# AMU_Version_3.net
KiCad netlist of a schematic drawn in Altium Designer
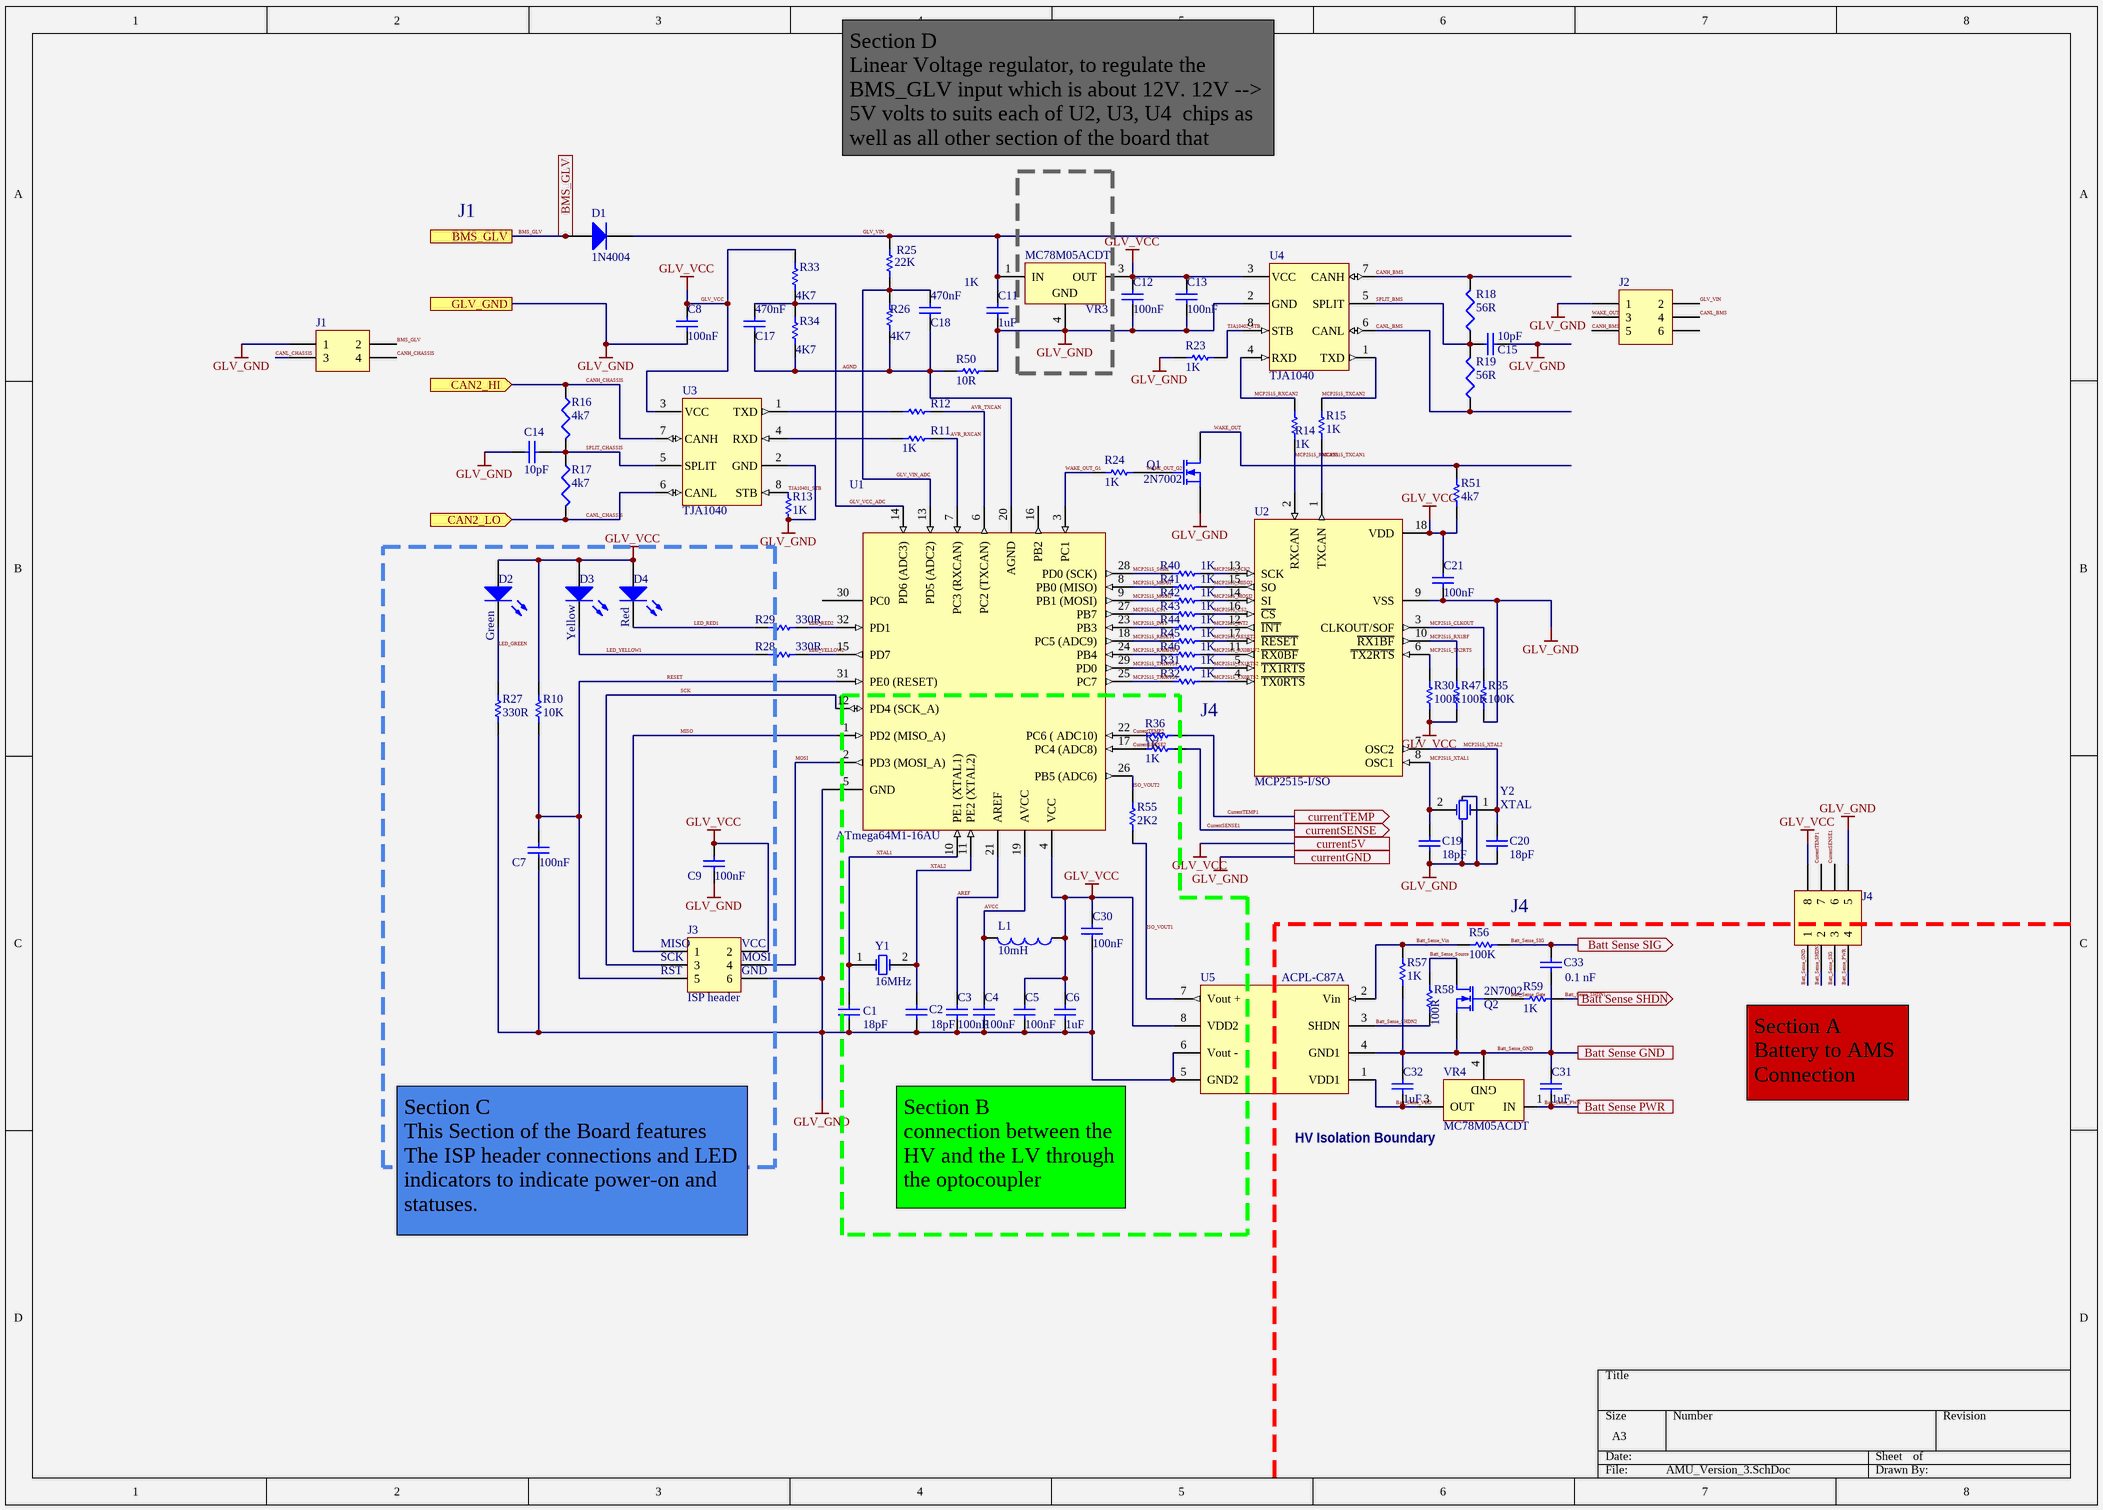
[diagram p0: AMU_Version_3.SchDoc]

(export (version "E")
  (design (tool "Eeschema 10.0.6"))
  (components
    (comp (ref "C1")
      (value "18pF")
      (footprint "1608[0603]")
      (description "Capacitor (Semiconductor SIM Model)")
      (fields (field (name "Comment") "Cap Semi") (field (name "PUBLISHER") "Altium Limited"))
      (libsource (lib "Miscellaneous Devices") (part "Cap Semi"))
    )
    (comp (ref "C2")
      (value "18pF")
      (footprint "1608[0603]")
      (description "Capacitor (Semiconductor SIM Model)")
      (fields (field (name "Comment") "Cap Semi") (field (name "PUBLISHER") "Altium Limited"))
      (libsource (lib "Miscellaneous Devices") (part "Cap Semi"))
    )
    (comp (ref "C3")
      (value "100nF")
      (footprint "1608[0603]")
      (description "Capacitor (Semiconductor SIM Model)")
      (fields (field (name "Comment") "Cap Semi") (field (name "PUBLISHER") "Altium Limited"))
      (libsource (lib "Miscellaneous Devices") (part "Cap Semi"))
    )
    (comp (ref "C4")
      (value "100nF")
      (footprint "1608[0603]")
      (description "Capacitor (Semiconductor SIM Model)")
      (fields (field (name "Comment") "Cap Semi") (field (name "PUBLISHER") "Altium Limited"))
      (libsource (lib "Miscellaneous Devices") (part "Cap Semi"))
    )
    (comp (ref "C5")
      (value "100nF")
      (footprint "1608[0603]")
      (description "Capacitor (Semiconductor SIM Model)")
      (fields (field (name "Comment") "Cap Semi") (field (name "PUBLISHER") "Altium Limited"))
      (libsource (lib "Miscellaneous Devices") (part "Cap Semi"))
    )
    (comp (ref "C6")
      (value "1uF")
      (footprint "1608[0603]")
      (description "Capacitor (Semiconductor SIM Model)")
      (fields (field (name "Comment") "Cap Semi") (field (name "PUBLISHER") "Altium Limited"))
      (libsource (lib "Miscellaneous Devices") (part "Cap Semi"))
    )
    (comp (ref "C7")
      (value "100nF")
      (footprint "1608[0603]")
      (description "Capacitor (Semiconductor SIM Model)")
      (fields (field (name "Comment") "Cap Semi") (field (name "PUBLISHER") "Altium Limited"))
      (libsource (lib "Miscellaneous Devices") (part "Cap Semi"))
    )
    (comp (ref "C8")
      (value "100nF")
      (footprint "1608[0603]")
      (description "Capacitor (Semiconductor SIM Model)")
      (fields (field (name "Comment") "Cap Semi") (field (name "PUBLISHER") "Altium Limited"))
      (libsource (lib "Miscellaneous Devices") (part "Cap Semi"))
    )
    (comp (ref "C9")
      (value "100nF")
      (footprint "1608[0603]")
      (description "Capacitor (Semiconductor SIM Model)")
      (fields (field (name "Comment") "Cap Semi") (field (name "PUBLISHER") "Altium Limited"))
      (libsource (lib "Miscellaneous Devices") (part "Cap Semi"))
    )
    (comp (ref "C11")
      (value "1uF")
      (footprint "1608[0603]")
      (description "Capacitor (Semiconductor SIM Model)")
      (fields (field (name "Comment") "Cap Semi") (field (name "PUBLISHER") "Altium Limited"))
      (libsource (lib "Miscellaneous Devices") (part "Cap Semi"))
    )
    (comp (ref "C12")
      (value "100nF")
      (footprint "1608[0603]")
      (description "Capacitor (Semiconductor SIM Model)")
      (fields (field (name "Comment") "Cap Semi") (field (name "PUBLISHER") "Altium Limited"))
      (libsource (lib "Miscellaneous Devices") (part "Cap Semi"))
    )
    (comp (ref "C13")
      (value "100nF")
      (footprint "1608[0603]")
      (description "Capacitor (Semiconductor SIM Model)")
      (fields (field (name "Comment") "Cap Semi") (field (name "PUBLISHER") "Altium Limited"))
      (libsource (lib "Miscellaneous Devices") (part "Cap Semi"))
    )
    (comp (ref "C14")
      (value "10pF")
      (footprint "1608[0603]")
      (description "Capacitor (Semiconductor SIM Model)")
      (fields (field (name "Comment") "Cap Semi") (field (name "PUBLISHER") "Altium Limited"))
      (libsource (lib "Miscellaneous Devices") (part "Cap Semi"))
    )
    (comp (ref "C15")
      (value "10pF")
      (footprint "1608[0603]")
      (description "Capacitor (Semiconductor SIM Model)")
      (fields (field (name "Comment") "Cap Semi") (field (name "PUBLISHER") "Altium Limited"))
      (libsource (lib "Miscellaneous Devices") (part "Cap Semi"))
    )
    (comp (ref "C17")
      (value "470nF")
      (footprint "1608[0603]")
      (description "Capacitor (Semiconductor SIM Model)")
      (fields (field (name "Comment") "Cap Semi") (field (name "PUBLISHER") "Altium Limited"))
      (libsource (lib "Miscellaneous Devices") (part "Cap Semi"))
    )
    (comp (ref "C18")
      (value "470nF")
      (footprint "1608[0603]")
      (description "Capacitor (Semiconductor SIM Model)")
      (fields (field (name "Comment") "Cap Semi") (field (name "PUBLISHER") "Altium Limited"))
      (libsource (lib "Miscellaneous Devices") (part "Cap Semi"))
    )
    (comp (ref "C19")
      (value "18pF")
      (footprint "1608[0603]")
      (description "Capacitor (Semiconductor SIM Model)")
      (fields (field (name "Comment") "Cap Semi") (field (name "PUBLISHER") "Altium Limited"))
      (libsource (lib "Miscellaneous Devices") (part "Cap Semi"))
    )
    (comp (ref "C20")
      (value "18pF")
      (footprint "1608[0603]")
      (description "Capacitor (Semiconductor SIM Model)")
      (fields (field (name "Comment") "Cap Semi") (field (name "PUBLISHER") "Altium Limited"))
      (libsource (lib "Miscellaneous Devices") (part "Cap Semi"))
    )
    (comp (ref "C21")
      (value "100nF")
      (footprint "1608[0603]")
      (description "Capacitor (Semiconductor SIM Model)")
      (fields (field (name "Comment") "Cap Semi") (field (name "PUBLISHER") "Altium Limited"))
      (libsource (lib "Miscellaneous Devices") (part "Cap Semi"))
    )
    (comp (ref "C30")
      (value "100nF")
      (footprint "1608[0603]")
      (description "Capacitor (Semiconductor SIM Model)")
      (fields (field (name "Comment") "Cap Semi") (field (name "PUBLISHER") "Altium Limited"))
      (libsource (lib "Miscellaneous Devices") (part "Cap Semi"))
    )
    (comp (ref "C31")
      (value "1uF")
      (footprint "1608[0603]")
      (description "Capacitor (Semiconductor SIM Model)")
      (fields (field (name "Comment") "Cap Semi") (field (name "PUBLISHER") "Altium Limited"))
      (libsource (lib "Miscellaneous Devices") (part "Cap Semi"))
    )
    (comp (ref "C32")
      (value "1uF")
      (footprint "1608[0603]")
      (description "Capacitor (Semiconductor SIM Model)")
      (fields (field (name "Comment") "Cap Semi") (field (name "PUBLISHER") "Altium Limited"))
      (libsource (lib "Miscellaneous Devices") (part "Cap Semi"))
    )
    (comp (ref "C33")
      (value "0.1 nF")
      (footprint "1608[0603]")
      (description "Capacitor (Semiconductor SIM Model)")
      (fields (field (name "Comment") "Cap Semi") (field (name "PUBLISHER") "Altium Limited"))
      (libsource (lib "Miscellaneous Devices") (part "Cap Semi"))
    )
    (comp (ref "D1")
      (value "1N4004")
      (footprint "PCBComponent_1")
      (description "Default Diode")
      (fields (field (name "PUBLISHER") "Altium Limited"))
      (libsource (lib "Miscellaneous Devices") (part "Diode"))
    )
    (comp (ref "D2")
      (value "Green")
      (footprint "0805_A")
      (description "Typical RED, GREEN, YELLOW, AMBER GaAs LED")
      (fields (field (name "PUBLISHER") "Altium Limited"))
      (libsource (lib "Miscellaneous Devices") (part "LED2"))
    )
    (comp (ref "D3")
      (value "Yellow")
      (footprint "0805_A")
      (description "Typical RED, GREEN, YELLOW, AMBER GaAs LED")
      (fields (field (name "PUBLISHER") "Altium Limited"))
      (libsource (lib "Miscellaneous Devices") (part "LED2"))
    )
    (comp (ref "D4")
      (value "Red")
      (footprint "0805_A")
      (description "Typical RED, GREEN, YELLOW, AMBER GaAs LED")
      (fields (field (name "PUBLISHER") "Altium Limited"))
      (libsource (lib "Miscellaneous Devices") (part "LED2"))
    )
    (comp (ref "J1")
      (value "Header 2X2")
      (footprint "HDR2X2")
      (description "Header, 2-Pin, Dual row")
      (fields (field (name "PUBLISHER") "Altium Limited"))
      (libsource (lib "Miscellaneous Connectors") (part "Header 2X2"))
    )
    (comp (ref "J2")
      (value "Header 3X2")
      (footprint "HDR2X3")
      (description "Header, 3-Pin, Dual row")
      (fields (field (name "PUBLISHER") "Altium Limited"))
      (libsource (lib "Miscellaneous Connectors") (part "Header 3X2"))
    )
    (comp (ref "J3")
      (value "ISP header")
      (footprint "HDR2X3")
      (description "Header, 3-Pin, Dual row")
      (fields (field (name "PUBLISHER") "Altium Limited"))
      (libsource (lib "Miscellaneous Connectors") (part "Header 3X2"))
    )
    (comp (ref "J4")
      (value "Header 4X2")
      (footprint "Miscellaneous Connectors:HDR2X4_CEN")
      (description "Header, 4-Pin, Dual row")
      (fields (field (name "PUBLISHER") "Altium Limited"))
      (libsource (lib "altium-import") (part "root_1_Header 4X2_"))
    )
    (comp (ref "L1")
      (value "10mH")
      (footprint "1608[0603]")
      (description "Inductor")
      (fields (field (name "PUBLISHER") "Altium Limited"))
      (libsource (lib "Miscellaneous Devices") (part "Inductor"))
    )
    (comp (ref "Q1")
      (value "2N7002")
      (footprint "SOT-23_N")
      (description "N-Channel MOSFET")
      (fields
        (field (name "MANUFACTURER") "NXP Semiconductors")
        (field (name "MANUFACTURER PART NUMBER") "2N7002P,215")
        (field (name "PUBLISHER") "Altium Limited")
      )
      (libsource (lib "") (part "MOSFET-N_1"))
    )
    (comp (ref "Q2")
      (value "2N7002")
      (footprint "SOT-23_L")
      (description "N-Channel MOSFET")
      (fields (field (name "PUBLISHER") "Altium Limited"))
      (libsource (lib "Miscellaneous Devices") (part "MOSFET-N"))
    )
    (comp (ref "R10")
      (value "10K")
      (footprint "6-0805_L")
      (description "Resistor")
      (fields (field (name "Comment") "Res1") (field (name "PUBLISHER") "Altium Limited"))
      (libsource (lib "Miscellaneous Devices") (part "Res1"))
    )
    (comp (ref "R11")
      (value "1K")
      (footprint "6-0805_L")
      (description "Resistor")
      (fields (field (name "Comment") "Res1") (field (name "PUBLISHER") "Altium Limited"))
      (libsource (lib "Miscellaneous Devices") (part "Res1"))
    )
    (comp (ref "R12")
      (value "1K")
      (footprint "6-0805_L")
      (description "Resistor")
      (fields (field (name "Comment") "Res1") (field (name "PUBLISHER") "Altium Limited"))
      (libsource (lib "Miscellaneous Devices") (part "Res1"))
    )
    (comp (ref "R13")
      (value "1K")
      (footprint "6-0805_L")
      (description "Resistor")
      (fields (field (name "Comment") "Res1") (field (name "PUBLISHER") "Altium Limited"))
      (libsource (lib "") (part "Res1_1"))
    )
    (comp (ref "R14")
      (value "1K")
      (footprint "6-0805_L")
      (description "Resistor")
      (fields (field (name "Comment") "Res1") (field (name "PUBLISHER") "Altium Limited"))
      (libsource (lib "Miscellaneous Devices") (part "Res1"))
    )
    (comp (ref "R15")
      (value "1K")
      (footprint "6-0805_L")
      (description "Resistor")
      (fields (field (name "Comment") "Res1") (field (name "PUBLISHER") "Altium Limited"))
      (libsource (lib "Miscellaneous Devices") (part "Res1"))
    )
    (comp (ref "R16")
      (value "4k7")
      (footprint "6-0805_L")
      (description "Resistor")
      (fields (field (name "Comment") "Res3") (field (name "PUBLISHER") "Altium Limited"))
      (libsource (lib "Miscellaneous Devices") (part "Res3"))
    )
    (comp (ref "R17")
      (value "4k7")
      (footprint "6-0805_L")
      (description "Resistor")
      (fields (field (name "Comment") "Res3") (field (name "PUBLISHER") "Altium Limited"))
      (libsource (lib "Miscellaneous Devices") (part "Res3"))
    )
    (comp (ref "R18")
      (value "56R")
      (footprint "6-0805_L")
      (description "Resistor")
      (fields (field (name "Comment") "Res3") (field (name "PUBLISHER") "Altium Limited"))
      (libsource (lib "Miscellaneous Devices") (part "Res3"))
    )
    (comp (ref "R19")
      (value "56R")
      (footprint "6-0805_L")
      (description "Resistor")
      (fields (field (name "Comment") "Res3") (field (name "PUBLISHER") "Altium Limited"))
      (libsource (lib "Miscellaneous Devices") (part "Res3"))
    )
    (comp (ref "R23")
      (value "1K")
      (footprint "6-0805_L")
      (description "Resistor")
      (fields (field (name "Comment") "Res1") (field (name "PUBLISHER") "Altium Limited"))
      (libsource (lib "Miscellaneous Devices") (part "Res1"))
    )
    (comp (ref "R24")
      (value "1K")
      (footprint "6-0805_L")
      (description "Resistor")
      (fields (field (name "Comment") "Res1") (field (name "PUBLISHER") "Altium Limited"))
      (libsource (lib "Miscellaneous Devices") (part "Res1"))
    )
    (comp (ref "R25")
      (value "22K")
      (footprint "6-0805_L")
      (description "Resistor")
      (fields (field (name "Comment") "Res1") (field (name "PUBLISHER") "Altium Limited"))
      (libsource (lib "Miscellaneous Devices") (part "Res1"))
    )
    (comp (ref "R26")
      (value "4K7")
      (footprint "6-0805_L")
      (description "Resistor")
      (fields (field (name "Comment") "Res1") (field (name "PUBLISHER") "Altium Limited"))
      (libsource (lib "Miscellaneous Devices") (part "Res1"))
    )
    (comp (ref "R27")
      (value "330R")
      (footprint "6-0805_L")
      (description "Resistor")
      (fields (field (name "Comment") "Res1") (field (name "PUBLISHER") "Altium Limited"))
      (libsource (lib "Miscellaneous Devices") (part "Res1"))
    )
    (comp (ref "R28")
      (value "330R")
      (footprint "6-0805_L")
      (description "Resistor")
      (fields (field (name "Comment") "Res1") (field (name "PUBLISHER") "Altium Limited"))
      (libsource (lib "Miscellaneous Devices") (part "Res1"))
    )
    (comp (ref "R29")
      (value "330R")
      (footprint "6-0805_L")
      (description "Resistor")
      (fields (field (name "Comment") "Res1") (field (name "PUBLISHER") "Altium Limited"))
      (libsource (lib "Miscellaneous Devices") (part "Res1"))
    )
    (comp (ref "R30")
      (value "100K")
      (footprint "6-0805_L")
      (description "Resistor")
      (fields (field (name "Comment") "Res1") (field (name "PUBLISHER") "Altium Limited"))
      (libsource (lib "Miscellaneous Devices") (part "Res1"))
    )
    (comp (ref "R31")
      (value "1K")
      (footprint "6-0805_L")
      (description "Resistor")
      (fields (field (name "Comment") "Res1") (field (name "PUBLISHER") "Altium Limited"))
      (libsource (lib "Miscellaneous Devices") (part "Res1"))
    )
    (comp (ref "R32")
      (value "1K")
      (footprint "6-0805_L")
      (description "Resistor")
      (fields (field (name "Comment") "Res1") (field (name "PUBLISHER") "Altium Limited"))
      (libsource (lib "Miscellaneous Devices") (part "Res1"))
    )
    (comp (ref "R33")
      (value "4K7")
      (footprint "6-0805_L")
      (description "Resistor")
      (fields (field (name "Comment") "Res1") (field (name "PUBLISHER") "Altium Limited"))
      (libsource (lib "Miscellaneous Devices") (part "Res1"))
    )
    (comp (ref "R34")
      (value "4K7")
      (footprint "6-0805_L")
      (description "Resistor")
      (fields (field (name "Comment") "Res1") (field (name "PUBLISHER") "Altium Limited"))
      (libsource (lib "Miscellaneous Devices") (part "Res1"))
    )
    (comp (ref "R35")
      (value "100K")
      (footprint "6-0805_L")
      (description "Resistor")
      (fields (field (name "Comment") "Res1") (field (name "PUBLISHER") "Altium Limited"))
      (libsource (lib "Miscellaneous Devices") (part "Res1"))
    )
    (comp (ref "R36")
      (value "1K")
      (footprint "6-0805_L")
      (description "Resistor")
      (fields (field (name "Comment") "Res1") (field (name "PUBLISHER") "Altium Limited"))
      (libsource (lib "Miscellaneous Devices") (part "Res1"))
    )
    (comp (ref "R37")
      (value "1K")
      (footprint "6-0805_L")
      (description "Resistor")
      (fields (field (name "Comment") "Res1") (field (name "PUBLISHER") "Altium Limited"))
      (libsource (lib "Miscellaneous Devices") (part "Res1"))
    )
    (comp (ref "R40")
      (value "1K")
      (footprint "6-0805_L")
      (description "Resistor")
      (fields (field (name "Comment") "Res1") (field (name "PUBLISHER") "Altium Limited"))
      (libsource (lib "Miscellaneous Devices") (part "Res1"))
    )
    (comp (ref "R41")
      (value "1K")
      (footprint "6-0805_L")
      (description "Resistor")
      (fields (field (name "Comment") "Res1") (field (name "PUBLISHER") "Altium Limited"))
      (libsource (lib "Miscellaneous Devices") (part "Res1"))
    )
    (comp (ref "R42")
      (value "1K")
      (footprint "6-0805_L")
      (description "Resistor")
      (fields (field (name "Comment") "Res1") (field (name "PUBLISHER") "Altium Limited"))
      (libsource (lib "Miscellaneous Devices") (part "Res1"))
    )
    (comp (ref "R43")
      (value "1K")
      (footprint "6-0805_L")
      (description "Resistor")
      (fields (field (name "Comment") "Res1") (field (name "PUBLISHER") "Altium Limited"))
      (libsource (lib "Miscellaneous Devices") (part "Res1"))
    )
    (comp (ref "R44")
      (value "1K")
      (footprint "6-0805_L")
      (description "Resistor")
      (fields (field (name "Comment") "Res1") (field (name "PUBLISHER") "Altium Limited"))
      (libsource (lib "Miscellaneous Devices") (part "Res1"))
    )
    (comp (ref "R45")
      (value "1K")
      (footprint "6-0805_L")
      (description "Resistor")
      (fields (field (name "Comment") "Res1") (field (name "PUBLISHER") "Altium Limited"))
      (libsource (lib "Miscellaneous Devices") (part "Res1"))
    )
    (comp (ref "R46")
      (value "1K")
      (footprint "6-0805_L")
      (description "Resistor")
      (fields (field (name "Comment") "Res1") (field (name "PUBLISHER") "Altium Limited"))
      (libsource (lib "Miscellaneous Devices") (part "Res1"))
    )
    (comp (ref "R47")
      (value "100K")
      (footprint "6-0805_L")
      (description "Resistor")
      (fields (field (name "Comment") "Res1") (field (name "PUBLISHER") "Altium Limited"))
      (libsource (lib "Miscellaneous Devices") (part "Res1"))
    )
    (comp (ref "R50")
      (value "10R")
      (footprint "6-0805_L")
      (description "Resistor")
      (fields (field (name "Comment") "Res1") (field (name "PUBLISHER") "Altium Limited"))
      (libsource (lib "Miscellaneous Devices") (part "Res1"))
    )
    (comp (ref "R51")
      (value "4k7")
      (footprint "6-0805_L")
      (description "Resistor")
      (fields (field (name "Comment") "Res1") (field (name "PUBLISHER") "Altium Limited"))
      (libsource (lib "Miscellaneous Devices") (part "Res1"))
    )
    (comp (ref "R55")
      (value "2K2")
      (footprint "6-0805_L")
      (description "Resistor")
      (fields (field (name "Comment") "Res1") (field (name "PUBLISHER") "Altium Limited"))
      (libsource (lib "Miscellaneous Devices") (part "Res1"))
    )
    (comp (ref "R56")
      (value "100K")
      (footprint "6-0805_L")
      (description "Resistor")
      (fields (field (name "Comment") "Res1") (field (name "PUBLISHER") "Altium Limited"))
      (libsource (lib "Miscellaneous Devices") (part "Res1"))
    )
    (comp (ref "R57")
      (value "1K")
      (footprint "6-0805_L")
      (description "Resistor")
      (fields (field (name "Comment") "Res1") (field (name "PUBLISHER") "Altium Limited"))
      (libsource (lib "Miscellaneous Devices") (part "Res1"))
    )
    (comp (ref "R58")
      (value "100R")
      (footprint "6-0805_L")
      (description "Resistor")
      (fields (field (name "Comment") "Res1") (field (name "PUBLISHER") "Altium Limited"))
      (libsource (lib "Miscellaneous Devices") (part "Res1"))
    )
    (comp (ref "R59")
      (value "1K")
      (footprint "6-0805_L")
      (description "Resistor")
      (fields (field (name "Comment") "Res1") (field (name "PUBLISHER") "Altium Limited"))
      (libsource (lib "Miscellaneous Devices") (part "Res1"))
    )
    (comp (ref "U1")
      (value "ATmega64M1-16AU")
      (footprint "32A_L")
      (description "8-Bit AVR Microcontroller with 8K Bytes of In-System Programmable Flash Memory")
      (fields (field (name "PUBLISHER") "Altium Limited"))
      (libsource (lib "Atmel Microcontroller 8-Bit AVR") (part "ATmega8-16AC"))
    )
    (comp (ref "U2")
      (value "MCP2515-I/SO")
      (footprint "MCP2515-I_SO:SOIC-SO18_M")
      (description "Stand-Alone CAN Controller With SPI Interface, 18-Pin SOIC, Industrial Temperature")
      (fields (field (name "PUBLISHER") "Altium Limited"))
      (libsource (lib "Microchip Interface") (part "MCP2515-I/SO"))
    )
    (comp (ref "U3")
      (value "TJA1040")
      (footprint "IC_NXP_TJA1040T-CM,118_eec_0:NXP_SOT96-1_0")
      (libsource (lib "IC_NXP_TJA1040T-CM,118_eec") (part "TJA1040"))
    )
    (comp (ref "U4")
      (value "TJA1040")
      (footprint "NXP_SOT96-1_0")
      (libsource (lib "Schlib1") (part "TJA1040"))
    )
    (comp (ref "U5")
      (value "ACPL-C87A")
      (footprint "Broadcom_SSO-8_IPC_A")
      (description "Isolated CAN transceiver")
      (fields (field (name "PUBLISHER") "Altium Limited"))
      (libsource (lib "Atmel Microcontroller 8-Bit AVR") (part "AT90S2343-10SI"))
    )
    (comp (ref "VR3")
      (value "MC78M05ACDT")
      (footprint "MC78M05ACDT")
      (description "Three-Terminal Medium Current Positive Voltage Regulator")
      (fields (field (name "PUBLISHER") "Altium Limited"))
      (libsource (lib "") (part "MC78M05ACDT_1"))
    )
    (comp (ref "VR4")
      (value "MC78M05ACDT")
      (footprint "MC78M05ACDT")
      (description "Three-Terminal Medium Current Positive Voltage Regulator")
      (fields (field (name "PUBLISHER") "Altium Limited"))
      (libsource (lib "ON Semi Power Mgt Voltage Regulator") (part "MC78M05ACDT"))
    )
    (comp (ref "Y1")
      (value "16MHz")
      (footprint "Crystal_Oscillator")
      (description "Crystal Oscillator")
      (fields (field (name "PUBLISHER") "Altium Limited"))
      (libsource (lib "Miscellaneous Devices") (part "XTAL"))
    )
    (comp (ref "Y2")
      (value "XTAL")
      (footprint "*XTAL_ECS-160-12-33Q-JES-TR")
      (description "Crystal Oscillator")
      (fields (field (name "PUBLISHER") "Altium Limited"))
      (libsource (lib "Schlib1") (part "XTAL"))
    )
  )
  (nets
    (net (code "1") (name "/AGND") (class "Default")
      (node (ref "C17") (pin "1") (pinfunction "1_1") (pintype "passive"))
      (node (ref "C18") (pin "1") (pinfunction "1_1") (pintype "passive"))
      (node (ref "R26") (pin "2") (pinfunction "2_2") (pintype "passive"))
      (node (ref "R34") (pin "2") (pinfunction "2_2") (pintype "passive"))
      (node (ref "R50") (pin "1") (pinfunction "1_1") (pintype "passive"))
      (node (ref "U1") (pin "20") (pinfunction "AGND_20") (pintype "power_in"))
    )
    (net (code "2") (name "/AREF") (class "Default")
      (node (ref "C3") (pin "1") (pinfunction "1_1") (pintype "passive"))
      (node (ref "U1") (pin "21") (pinfunction "AREF_21") (pintype "power_in"))
    )
    (net (code "3") (name "/AVCC") (class "Default")
      (node (ref "C4") (pin "1") (pinfunction "1_1") (pintype "passive"))
      (node (ref "L1") (pin "2") (pinfunction "2_2") (pintype "passive"))
      (node (ref "U1") (pin "19") (pinfunction "AVCC_19") (pintype "power_in"))
    )
    (net (code "4") (name "/AVR_RXCAN") (class "Default")
      (node (ref "R11") (pin "2") (pinfunction "2_2") (pintype "passive"))
      (node (ref "U1") (pin "7") (pinfunction "PC3_(RXCAN)_7") (pintype "input"))
    )
    (net (code "5") (name "/AVR_TXCAN") (class "Default")
      (node (ref "R12") (pin "1") (pinfunction "1_1") (pintype "passive"))
      (node (ref "U1") (pin "6") (pinfunction "PC2_(TXCAN)_6") (pintype "output"))
    )
    (net (code "6") (name "/BMS_GLV") (class "Default")
      (node (ref "D1") (pin "1") (pinfunction "A_1") (pintype "passive"))
      (node (ref "J1") (pin "2") (pinfunction "2_2") (pintype "passive"))
    )
    (net (code "7") (name "/Batt_Sense_GND") (class "Default")
      (node (ref "C31") (pin "2") (pinfunction "2_2") (pintype "passive"))
      (node (ref "C32") (pin "2") (pinfunction "2_2") (pintype "passive"))
      (node (ref "C33") (pin "1") (pinfunction "1_1") (pintype "passive"))
      (node (ref "J4") (pin "1") (pinfunction "1_1") (pintype "passive"))
      (node (ref "Q2") (pin "2") (pinfunction "S_2") (pintype "passive"))
      (node (ref "R57") (pin "1") (pinfunction "1_1") (pintype "passive"))
      (node (ref "U5") (pin "4") (pinfunction "GND1_4") (pintype "power_in"))
      (node (ref "VR4") (pin "4") (pinfunction "GND_4") (pintype "power_in"))
    )
    (net (code "8") (name "/Batt_Sense_Gate") (class "Default")
      (node (ref "Q2") (pin "1") (pinfunction "G_1") (pintype "passive"))
      (node (ref "R59") (pin "2") (pinfunction "2_2") (pintype "passive"))
    )
    (net (code "9") (name "/Batt_Sense_PWR") (class "Default")
      (node (ref "C31") (pin "1") (pinfunction "1_1") (pintype "passive"))
      (node (ref "J4") (pin "4") (pinfunction "4_4") (pintype "passive"))
      (node (ref "VR4") (pin "1") (pinfunction "IN_1") (pintype "power_in"))
    )
    (net (code "10") (name "/Batt_Sense_SHDN1") (class "Default")
      (node (ref "J4") (pin "2") (pinfunction "2_2") (pintype "passive"))
      (node (ref "R59") (pin "1") (pinfunction "1_1") (pintype "passive"))
    )
    (net (code "11") (name "/Batt_Sense_SHDN2") (class "Default")
      (node (ref "R58") (pin "1") (pinfunction "1_1") (pintype "passive"))
      (node (ref "U5") (pin "3") (pinfunction "SHDN_3") (pintype "open_collector"))
    )
    (net (code "12") (name "/Batt_Sense_SIG") (class "Default")
      (node (ref "C33") (pin "2") (pinfunction "2_2") (pintype "passive"))
      (node (ref "J4") (pin "3") (pinfunction "3_3") (pintype "passive"))
      (node (ref "R56") (pin "1") (pinfunction "1_1") (pintype "passive"))
    )
    (net (code "13") (name "/Batt_Sense_Source") (class "Default")
      (node (ref "Q2") (pin "3") (pinfunction "D_3") (pintype "passive"))
      (node (ref "R58") (pin "2") (pinfunction "2_2") (pintype "passive"))
    )
    (net (code "14") (name "/Batt_Sense_VDD") (class "Default")
      (node (ref "C32") (pin "1") (pinfunction "1_1") (pintype "passive"))
      (node (ref "U5") (pin "1") (pinfunction "VDD1_1") (pintype "power_in"))
      (node (ref "VR4") (pin "3") (pinfunction "OUT_3") (pintype "power_in"))
    )
    (net (code "15") (name "/Batt_Sense_Vin") (class "Default")
      (node (ref "R56") (pin "2") (pinfunction "2_2") (pintype "passive"))
      (node (ref "R57") (pin "2") (pinfunction "2_2") (pintype "passive"))
      (node (ref "U5") (pin "2") (pinfunction "Vin_2") (pintype "input"))
    )
    (net (code "16") (name "/CANH_BMS") (class "Default")
      (node (ref "J2") (pin "5") (pinfunction "5_5") (pintype "passive"))
      (node (ref "R18") (pin "2") (pinfunction "2_2") (pintype "passive"))
      (node (ref "U4") (pin "7") (pinfunction "CANH_7") (pintype "bidirectional"))
    )
    (net (code "17") (name "/CANH_CHASSIS") (class "Default")
      (node (ref "J1") (pin "4") (pinfunction "4_4") (pintype "passive"))
      (node (ref "R16") (pin "1") (pinfunction "1_1") (pintype "passive"))
      (node (ref "U3") (pin "7") (pinfunction "CANH_7") (pintype "bidirectional"))
    )
    (net (code "18") (name "/CANL_BMS") (class "Default")
      (node (ref "J2") (pin "4") (pinfunction "4_4") (pintype "passive"))
      (node (ref "R19") (pin "1") (pinfunction "1_1") (pintype "passive"))
      (node (ref "U4") (pin "6") (pinfunction "CANL_6") (pintype "bidirectional"))
    )
    (net (code "19") (name "/CANL_CHASSIS") (class "Default")
      (node (ref "J1") (pin "3") (pinfunction "3_3") (pintype "passive"))
      (node (ref "R17") (pin "2") (pinfunction "2_2") (pintype "passive"))
      (node (ref "U3") (pin "6") (pinfunction "CANL_6") (pintype "bidirectional"))
    )
    (net (code "20") (name "/CurrentSENSE1") (class "Default")
      (node (ref "J4") (pin "6") (pinfunction "6_6") (pintype "passive"))
      (node (ref "R37") (pin "1") (pinfunction "1_1") (pintype "passive"))
    )
    (net (code "21") (name "/CurrentSENSE2") (class "Default")
      (node (ref "R37") (pin "2") (pinfunction "2_2") (pintype "passive"))
      (node (ref "U1") (pin "17") (pinfunction "PC4_(ADC8)_17") (pintype "input"))
    )
    (net (code "22") (name "/CurrentTEMP1") (class "Default")
      (node (ref "J4") (pin "7") (pinfunction "7_7") (pintype "passive"))
      (node (ref "R36") (pin "1") (pinfunction "1_1") (pintype "passive"))
    )
    (net (code "23") (name "/CurrentTEMP2") (class "Default")
      (node (ref "R36") (pin "2") (pinfunction "2_2") (pintype "passive"))
      (node (ref "U1") (pin "22") (pinfunction "PC6_(_ADC10)_22") (pintype "input"))
    )
    (net (code "24") (name "/GLV_VCC_ADC") (class "Default")
      (node (ref "C17") (pin "2") (pinfunction "2_2") (pintype "passive"))
      (node (ref "R33") (pin "2") (pinfunction "2_2") (pintype "passive"))
      (node (ref "R34") (pin "1") (pinfunction "1_1") (pintype "passive"))
      (node (ref "U1") (pin "14") (pinfunction "PD6_(ADC3)_14") (pintype "input"))
    )
    (net (code "25") (name "/GLV_VIN") (class "Default")
      (node (ref "C11") (pin "2") (pinfunction "2_2") (pintype "passive"))
      (node (ref "D1") (pin "2") (pinfunction "K_2") (pintype "passive"))
      (node (ref "J2") (pin "2") (pinfunction "2_2") (pintype "passive"))
      (node (ref "R25") (pin "1") (pinfunction "1_1") (pintype "passive"))
      (node (ref "VR3") (pin "1") (pinfunction "IN_1") (pintype "power_in"))
    )
    (net (code "26") (name "/GLV_VIN_ADC") (class "Default")
      (node (ref "C18") (pin "2") (pinfunction "2_2") (pintype "passive"))
      (node (ref "R25") (pin "2") (pinfunction "2_2") (pintype "passive"))
      (node (ref "R26") (pin "1") (pinfunction "1_1") (pintype "passive"))
      (node (ref "U1") (pin "13") (pinfunction "PD5_(ADC2)_13") (pintype "input"))
    )
    (net (code "27") (name "/ISO_VOUT1") (class "Default")
      (node (ref "R55") (pin "2") (pinfunction "2_2") (pintype "passive"))
      (node (ref "U5") (pin "7") (pinfunction "Vout_+_7") (pintype "output"))
    )
    (net (code "28") (name "/ISO_VOUT2") (class "Default")
      (node (ref "R55") (pin "1") (pinfunction "1_1") (pintype "passive"))
      (node (ref "U1") (pin "26") (pinfunction "PB5_(ADC6)_26") (pintype "output"))
    )
    (net (code "29") (name "/LED_GREEN") (class "Default")
      (node (ref "D2") (pin "2") (pinfunction "K_2") (pintype "passive"))
      (node (ref "R27") (pin "2") (pinfunction "2_2") (pintype "passive"))
    )
    (net (code "30") (name "/LED_RED1") (class "Default")
      (node (ref "D4") (pin "2") (pinfunction "K_2") (pintype "passive"))
      (node (ref "R29") (pin "1") (pinfunction "1_1") (pintype "passive"))
    )
    (net (code "31") (name "/LED_RED2") (class "Default")
      (node (ref "R29") (pin "2") (pinfunction "2_2") (pintype "passive"))
      (node (ref "U1") (pin "32") (pinfunction "PD1_32") (pintype "input"))
    )
    (net (code "32") (name "/LED_YELLOW1") (class "Default")
      (node (ref "D3") (pin "2") (pinfunction "K_2") (pintype "passive"))
      (node (ref "R28") (pin "1") (pinfunction "1_1") (pintype "passive"))
    )
    (net (code "33") (name "/LED_YELLOW2") (class "Default")
      (node (ref "R28") (pin "2") (pinfunction "2_2") (pintype "passive"))
      (node (ref "U1") (pin "15") (pinfunction "PD7_15") (pintype "output"))
    )
    (net (code "34") (name "/MCP2515_CLKOUT") (class "Default")
      (node (ref "R35") (pin "2") (pinfunction "2_2") (pintype "passive"))
      (node (ref "U2") (pin "3") (pinfunction "CLKOUT/SOF_3") (pintype "output"))
    )
    (net (code "35") (name "/MCP2515_CS1") (class "Default")
      (node (ref "R43") (pin "1") (pinfunction "1_1") (pintype "passive"))
      (node (ref "U1") (pin "27") (pinfunction "PB7_27") (pintype "output"))
    )
    (net (code "36") (name "/MCP2515_CS2") (class "Default")
      (node (ref "R43") (pin "2") (pinfunction "2_2") (pintype "passive"))
      (node (ref "U2") (pin "16") (pinfunction "~{CS}_16") (pintype "input"))
    )
    (net (code "37") (name "/MCP2515_INT1") (class "Default")
      (node (ref "R44") (pin "1") (pinfunction "1_1") (pintype "passive"))
      (node (ref "U1") (pin "23") (pinfunction "PB3_23") (pintype "input"))
    )
    (net (code "38") (name "/MCP2515_INT2") (class "Default")
      (node (ref "R44") (pin "2") (pinfunction "2_2") (pintype "passive"))
      (node (ref "U2") (pin "12") (pinfunction "~{INT}_12") (pintype "output"))
    )
    (net (code "39") (name "/MCP2515_MISO1") (class "Default")
      (node (ref "R41") (pin "1") (pinfunction "1_1") (pintype "passive"))
      (node (ref "U1") (pin "8") (pinfunction "PB0_(MISO)_8") (pintype "input"))
    )
    (net (code "40") (name "/MCP2515_MISO2") (class "Default")
      (node (ref "R41") (pin "2") (pinfunction "2_2") (pintype "passive"))
      (node (ref "U2") (pin "15") (pinfunction "SO_15") (pintype "output"))
    )
    (net (code "41") (name "/MCP2515_MOSI1") (class "Default")
      (node (ref "R42") (pin "1") (pinfunction "1_1") (pintype "passive"))
      (node (ref "U1") (pin "9") (pinfunction "PB1_(MOSI)_9") (pintype "output"))
    )
    (net (code "42") (name "/MCP2515_MOSI2") (class "Default")
      (node (ref "R42") (pin "2") (pinfunction "2_2") (pintype "passive"))
      (node (ref "U2") (pin "14") (pinfunction "SI_14") (pintype "input"))
    )
    (net (code "43") (name "/MCP2515_RESET1") (class "Default")
      (node (ref "R45") (pin "1") (pinfunction "1_1") (pintype "passive"))
      (node (ref "U1") (pin "18") (pinfunction "PC5_(ADC9)_18") (pintype "output"))
    )
    (net (code "44") (name "/MCP2515_RESET2") (class "Default")
      (node (ref "R45") (pin "2") (pinfunction "2_2") (pintype "passive"))
      (node (ref "U2") (pin "17") (pinfunction "~{RESET}_17") (pintype "input"))
    )
    (net (code "45") (name "/MCP2515_RX0BUF1") (class "Default")
      (node (ref "R46") (pin "1") (pinfunction "1_1") (pintype "passive"))
      (node (ref "U1") (pin "24") (pinfunction "PB4_24") (pintype "input"))
    )
    (net (code "46") (name "/MCP2515_RX0BUF2") (class "Default")
      (node (ref "R46") (pin "2") (pinfunction "2_2") (pintype "passive"))
      (node (ref "U2") (pin "11") (pinfunction "~{RX0BF}_11") (pintype "output"))
    )
    (net (code "47") (name "/MCP2515_RX1BF") (class "Default")
      (node (ref "R47") (pin "2") (pinfunction "2_2") (pintype "passive"))
      (node (ref "U2") (pin "10") (pinfunction "~{RX1BF}_10") (pintype "output"))
    )
    (net (code "48") (name "/MCP2515_RXCAN1") (class "Default")
      (node (ref "R14") (pin "2") (pinfunction "2_2") (pintype "passive"))
      (node (ref "U2") (pin "2") (pinfunction "RXCAN_2") (pintype "input"))
    )
    (net (code "49") (name "/MCP2515_RXCAN2") (class "Default")
      (node (ref "R14") (pin "1") (pinfunction "1_1") (pintype "passive"))
      (node (ref "U4") (pin "4") (pinfunction "RXD_4") (pintype "input"))
    )
    (net (code "50") (name "/MCP2515_SCK1") (class "Default")
      (node (ref "R40") (pin "1") (pinfunction "1_1") (pintype "passive"))
      (node (ref "U1") (pin "28") (pinfunction "PD0_(SCK)_28") (pintype "output"))
    )
    (net (code "51") (name "/MCP2515_SCK2") (class "Default")
      (node (ref "R40") (pin "2") (pinfunction "2_2") (pintype "passive"))
      (node (ref "U2") (pin "13") (pinfunction "SCK_13") (pintype "input"))
    )
    (net (code "52") (name "/MCP2515_TX0RTS1") (class "Default")
      (node (ref "R32") (pin "1") (pinfunction "1_1") (pintype "passive"))
      (node (ref "U1") (pin "25") (pinfunction "PC7_25") (pintype "output"))
    )
    (net (code "53") (name "/MCP2515_TX0RTS2") (class "Default")
      (node (ref "R32") (pin "2") (pinfunction "2_2") (pintype "passive"))
      (node (ref "U2") (pin "4") (pinfunction "~{TX0RTS}_4") (pintype "input"))
    )
    (net (code "54") (name "/MCP2515_TX1RTS1") (class "Default")
      (node (ref "R31") (pin "1") (pinfunction "1_1") (pintype "passive"))
      (node (ref "U1") (pin "29") (pinfunction "PD0_29") (pintype "output"))
    )
    (net (code "55") (name "/MCP2515_TX1RTS2") (class "Default")
      (node (ref "R31") (pin "2") (pinfunction "2_2") (pintype "passive"))
      (node (ref "U2") (pin "5") (pinfunction "~{TX1RTS}_5") (pintype "input"))
    )
    (net (code "56") (name "/MCP2515_TX2RTS") (class "Default")
      (node (ref "R30") (pin "2") (pinfunction "2_2") (pintype "passive"))
      (node (ref "U2") (pin "6") (pinfunction "~{TX2RTS}_6") (pintype "input"))
    )
    (net (code "57") (name "/MCP2515_TXCAN1") (class "Default")
      (node (ref "R15") (pin "2") (pinfunction "2_2") (pintype "passive"))
      (node (ref "U2") (pin "1") (pinfunction "TXCAN_1") (pintype "output"))
    )
    (net (code "58") (name "/MCP2515_TXCAN2") (class "Default")
      (node (ref "R15") (pin "1") (pinfunction "1_1") (pintype "passive"))
      (node (ref "U4") (pin "1") (pinfunction "TXD_1") (pintype "output"))
    )
    (net (code "59") (name "/MCP2515_XTAL1") (class "Default")
      (node (ref "C19") (pin "1") (pinfunction "1_1") (pintype "passive"))
      (node (ref "U2") (pin "8") (pinfunction "OSC1_8") (pintype "input"))
      (node (ref "Y2") (pin "2") (pinfunction "OSC2_2") (pintype "passive"))
    )
    (net (code "60") (name "/MCP2515_XTAL2") (class "Default")
      (node (ref "C20") (pin "2") (pinfunction "2_2") (pintype "passive"))
      (node (ref "U2") (pin "7") (pinfunction "OSC2_7") (pintype "output"))
      (node (ref "Y2") (pin "1") (pinfunction "OSC1_1") (pintype "passive"))
    )
    (net (code "61") (name "/MISO") (class "Default")
      (node (ref "J3") (pin "1") (pinfunction "1_1") (pintype "passive"))
      (node (ref "U1") (pin "1") (pinfunction "PD2_(MISO_A)_1") (pintype "input"))
    )
    (net (code "62") (name "/MOSI") (class "Default")
      (node (ref "J3") (pin "4") (pinfunction "4_4") (pintype "passive"))
      (node (ref "U1") (pin "2") (pinfunction "PD3_(MOSI_A)_2") (pintype "output"))
    )
    (net (code "63") (name "/RESET") (class "Default")
      (node (ref "C7") (pin "2") (pinfunction "2_2") (pintype "passive"))
      (node (ref "J3") (pin "5") (pinfunction "5_5") (pintype "passive"))
      (node (ref "R10") (pin "1") (pinfunction "1_1") (pintype "passive"))
      (node (ref "U1") (pin "31") (pinfunction "PE0_(RESET)_31") (pintype "input"))
    )
    (net (code "64") (name "/SCK") (class "Default")
      (node (ref "J3") (pin "3") (pinfunction "3_3") (pintype "passive"))
      (node (ref "U1") (pin "12") (pinfunction "PD4_(SCK_A)_12") (pintype "bidirectional"))
    )
    (net (code "65") (name "/SPLIT_BMS") (class "Default")
      (node (ref "C15") (pin "2") (pinfunction "2_2") (pintype "passive"))
      (node (ref "R18") (pin "1") (pinfunction "1_1") (pintype "passive"))
      (node (ref "R19") (pin "2") (pinfunction "2_2") (pintype "passive"))
      (node (ref "U4") (pin "5") (pinfunction "SPLIT_5") (pintype "power_in"))
    )
    (net (code "66") (name "/SPLIT_CHASSIS") (class "Default")
      (node (ref "C14") (pin "2") (pinfunction "2_2") (pintype "passive"))
      (node (ref "R16") (pin "2") (pinfunction "2_2") (pintype "passive"))
      (node (ref "R17") (pin "1") (pinfunction "1_1") (pintype "passive"))
      (node (ref "U3") (pin "5") (pinfunction "SPLIT_5") (pintype "power_in"))
    )
    (net (code "67") (name "/TJA10401_STB") (class "Default")
      (node (ref "R13") (pin "2") (pinfunction "2_2") (pintype "passive"))
      (node (ref "U3") (pin "8") (pinfunction "STB_8") (pintype "input"))
    )
    (net (code "68") (name "/TJA10402_STB") (class "Default")
      (node (ref "R23") (pin "2") (pinfunction "2_2") (pintype "passive"))
      (node (ref "U4") (pin "8") (pinfunction "STB_8") (pintype "input"))
    )
    (net (code "69") (name "/WAKE_OUT") (class "Default")
      (node (ref "J2") (pin "3") (pinfunction "3_3") (pintype "passive"))
      (node (ref "Q1") (pin "3") (pinfunction "D_3") (pintype "passive"))
      (node (ref "R51") (pin "2") (pinfunction "2_2") (pintype "passive"))
    )
    (net (code "70") (name "/WAKE_OUT_G1") (class "Default")
      (node (ref "R24") (pin "1") (pinfunction "1_1") (pintype "passive"))
      (node (ref "U1") (pin "3") (pinfunction "PC1_3") (pintype "input"))
    )
    (net (code "71") (name "/WAKE_OUT_G2") (class "Default")
      (node (ref "Q1") (pin "1") (pinfunction "G_1") (pintype "passive"))
      (node (ref "R24") (pin "2") (pinfunction "2_2") (pintype "passive"))
    )
    (net (code "72") (name "/XTAL1") (class "Default")
      (node (ref "C1") (pin "2") (pinfunction "2_2") (pintype "passive"))
      (node (ref "U1") (pin "10") (pinfunction "PE1_(XTAL1)_10") (pintype "input"))
      (node (ref "Y1") (pin "1") (pinfunction "OSC1_1") (pintype "passive"))
    )
    (net (code "73") (name "/XTAL2") (class "Default")
      (node (ref "C2") (pin "2") (pinfunction "2_2") (pintype "passive"))
      (node (ref "U1") (pin "11") (pinfunction "PE2_(XTAL2)_11") (pintype "input"))
      (node (ref "Y1") (pin "2") (pinfunction "OSC2_2") (pintype "passive"))
    )
    (net (code "74") (name "GLV_GND") (class "Default")
      (node (ref "C1") (pin "1") (pinfunction "1_1") (pintype "passive"))
      (node (ref "C11") (pin "1") (pinfunction "1_1") (pintype "passive"))
      (node (ref "C12") (pin "1") (pinfunction "1_1") (pintype "passive"))
      (node (ref "C13") (pin "1") (pinfunction "1_1") (pintype "passive"))
      (node (ref "C14") (pin "1") (pinfunction "1_1") (pintype "passive"))
      (node (ref "C15") (pin "1") (pinfunction "1_1") (pintype "passive"))
      (node (ref "C19") (pin "2") (pinfunction "2_2") (pintype "passive"))
      (node (ref "C2") (pin "1") (pinfunction "1_1") (pintype "passive"))
      (node (ref "C20") (pin "1") (pinfunction "1_1") (pintype "passive"))
      (node (ref "C21") (pin "1") (pinfunction "1_1") (pintype "passive"))
      (node (ref "C3") (pin "2") (pinfunction "2_2") (pintype "passive"))
      (node (ref "C30") (pin "2") (pinfunction "2_2") (pintype "passive"))
      (node (ref "C4") (pin "2") (pinfunction "2_2") (pintype "passive"))
      (node (ref "C5") (pin "2") (pinfunction "2_2") (pintype "passive"))
      (node (ref "C6") (pin "2") (pinfunction "2_2") (pintype "passive"))
      (node (ref "C7") (pin "1") (pinfunction "1_1") (pintype "passive"))
      (node (ref "C8") (pin "1") (pinfunction "1_1") (pintype "passive"))
      (node (ref "C9") (pin "1") (pinfunction "1_1") (pintype "passive"))
      (node (ref "J1") (pin "1") (pinfunction "1_1") (pintype "passive"))
      (node (ref "J2") (pin "1") (pinfunction "1_1") (pintype "passive"))
      (node (ref "J3") (pin "6") (pinfunction "6_6") (pintype "passive"))
      (node (ref "J4") (pin "5") (pinfunction "5_5") (pintype "passive"))
      (node (ref "Q1") (pin "2") (pinfunction "S_2") (pintype "passive"))
      (node (ref "R13") (pin "1") (pinfunction "1_1") (pintype "passive"))
      (node (ref "R23") (pin "1") (pinfunction "1_1") (pintype "passive"))
      (node (ref "R27") (pin "1") (pinfunction "1_1") (pintype "passive"))
      (node (ref "R35") (pin "1") (pinfunction "1_1") (pintype "passive"))
      (node (ref "R50") (pin "2") (pinfunction "2_2") (pintype "passive"))
      (node (ref "U1") (pin "5") (pinfunction "GND_5") (pintype "power_in"))
      (node (ref "U2") (pin "9") (pinfunction "VSS_9") (pintype "power_in"))
      (node (ref "U3") (pin "2") (pinfunction "GND_2") (pintype "power_in"))
      (node (ref "U4") (pin "2") (pinfunction "GND_2") (pintype "power_in"))
      (node (ref "U5") (pin "5") (pinfunction "GND2_5") (pintype "power_in"))
      (node (ref "U5") (pin "6") (pinfunction "Vout_-_6") (pintype "power_in"))
      (node (ref "VR3") (pin "4") (pinfunction "GND_4") (pintype "power_in"))
      (node (ref "Y2") (pin "3") (pinfunction "3_3") (pintype "passive"))
      (node (ref "Y2") (pin "4") (pinfunction "4_4") (pintype "passive"))
    )
    (net (code "75") (name "GLV_VCC") (class "Default")
      (node (ref "C12") (pin "2") (pinfunction "2_2") (pintype "passive"))
      (node (ref "C13") (pin "2") (pinfunction "2_2") (pintype "passive"))
      (node (ref "C21") (pin "2") (pinfunction "2_2") (pintype "passive"))
      (node (ref "C30") (pin "1") (pinfunction "1_1") (pintype "passive"))
      (node (ref "C5") (pin "1") (pinfunction "1_1") (pintype "passive"))
      (node (ref "C6") (pin "1") (pinfunction "1_1") (pintype "passive"))
      (node (ref "C8") (pin "2") (pinfunction "2_2") (pintype "passive"))
      (node (ref "C9") (pin "2") (pinfunction "2_2") (pintype "passive"))
      (node (ref "D2") (pin "1") (pinfunction "A_1") (pintype "passive"))
      (node (ref "D3") (pin "1") (pinfunction "A_1") (pintype "passive"))
      (node (ref "D4") (pin "1") (pinfunction "A_1") (pintype "passive"))
      (node (ref "J3") (pin "2") (pinfunction "2_2") (pintype "passive"))
      (node (ref "J4") (pin "8") (pinfunction "8_8") (pintype "passive"))
      (node (ref "L1") (pin "1") (pinfunction "1_1") (pintype "passive"))
      (node (ref "R10") (pin "2") (pinfunction "2_2") (pintype "passive"))
      (node (ref "R30") (pin "1") (pinfunction "1_1") (pintype "passive"))
      (node (ref "R33") (pin "1") (pinfunction "1_1") (pintype "passive"))
      (node (ref "R47") (pin "1") (pinfunction "1_1") (pintype "passive"))
      (node (ref "R51") (pin "1") (pinfunction "1_1") (pintype "passive"))
      (node (ref "U1") (pin "4") (pinfunction "VCC_4") (pintype "power_in"))
      (node (ref "U2") (pin "18") (pinfunction "VDD_18") (pintype "power_in"))
      (node (ref "U3") (pin "3") (pinfunction "VCC_3") (pintype "passive"))
      (node (ref "U4") (pin "3") (pinfunction "VCC_3") (pintype "passive"))
      (node (ref "U5") (pin "8") (pinfunction "VDD2_8") (pintype "power_in"))
      (node (ref "VR3") (pin "3") (pinfunction "OUT_3") (pintype "power_in"))
    )
    (net (code "76") (name "Net-(U3-RXD)") (class "Default")
      (node (ref "R11") (pin "1") (pinfunction "1_1") (pintype "passive"))
      (node (ref "U3") (pin "4") (pinfunction "RXD_4") (pintype "input"))
    )
    (net (code "77") (name "Net-(U3-TXD)") (class "Default")
      (node (ref "R12") (pin "2") (pinfunction "2_2") (pintype "passive"))
      (node (ref "U3") (pin "1") (pinfunction "TXD_1") (pintype "output"))
    )
    (net (code "78") (name "unconnected-(J2-Pad6)") (class "Default")
      (node (ref "J2") (pin "6") (pinfunction "6_6") (pintype "passive"))
    )
    (net (code "79") (name "unconnected-(U1-PB2-Pad16)") (class "Default")
      (node (ref "U1") (pin "16") (pinfunction "PB2_16") (pintype "output"))
    )
    (net (code "80") (name "unconnected-(U1-PC0-Pad30)") (class "Default")
      (node (ref "U1") (pin "30") (pinfunction "PC0_30") (pintype "passive"))
    )
  )
)
